# DWM1000_Feather.net
KiCad netlist of a schematic drawn in EAGLE
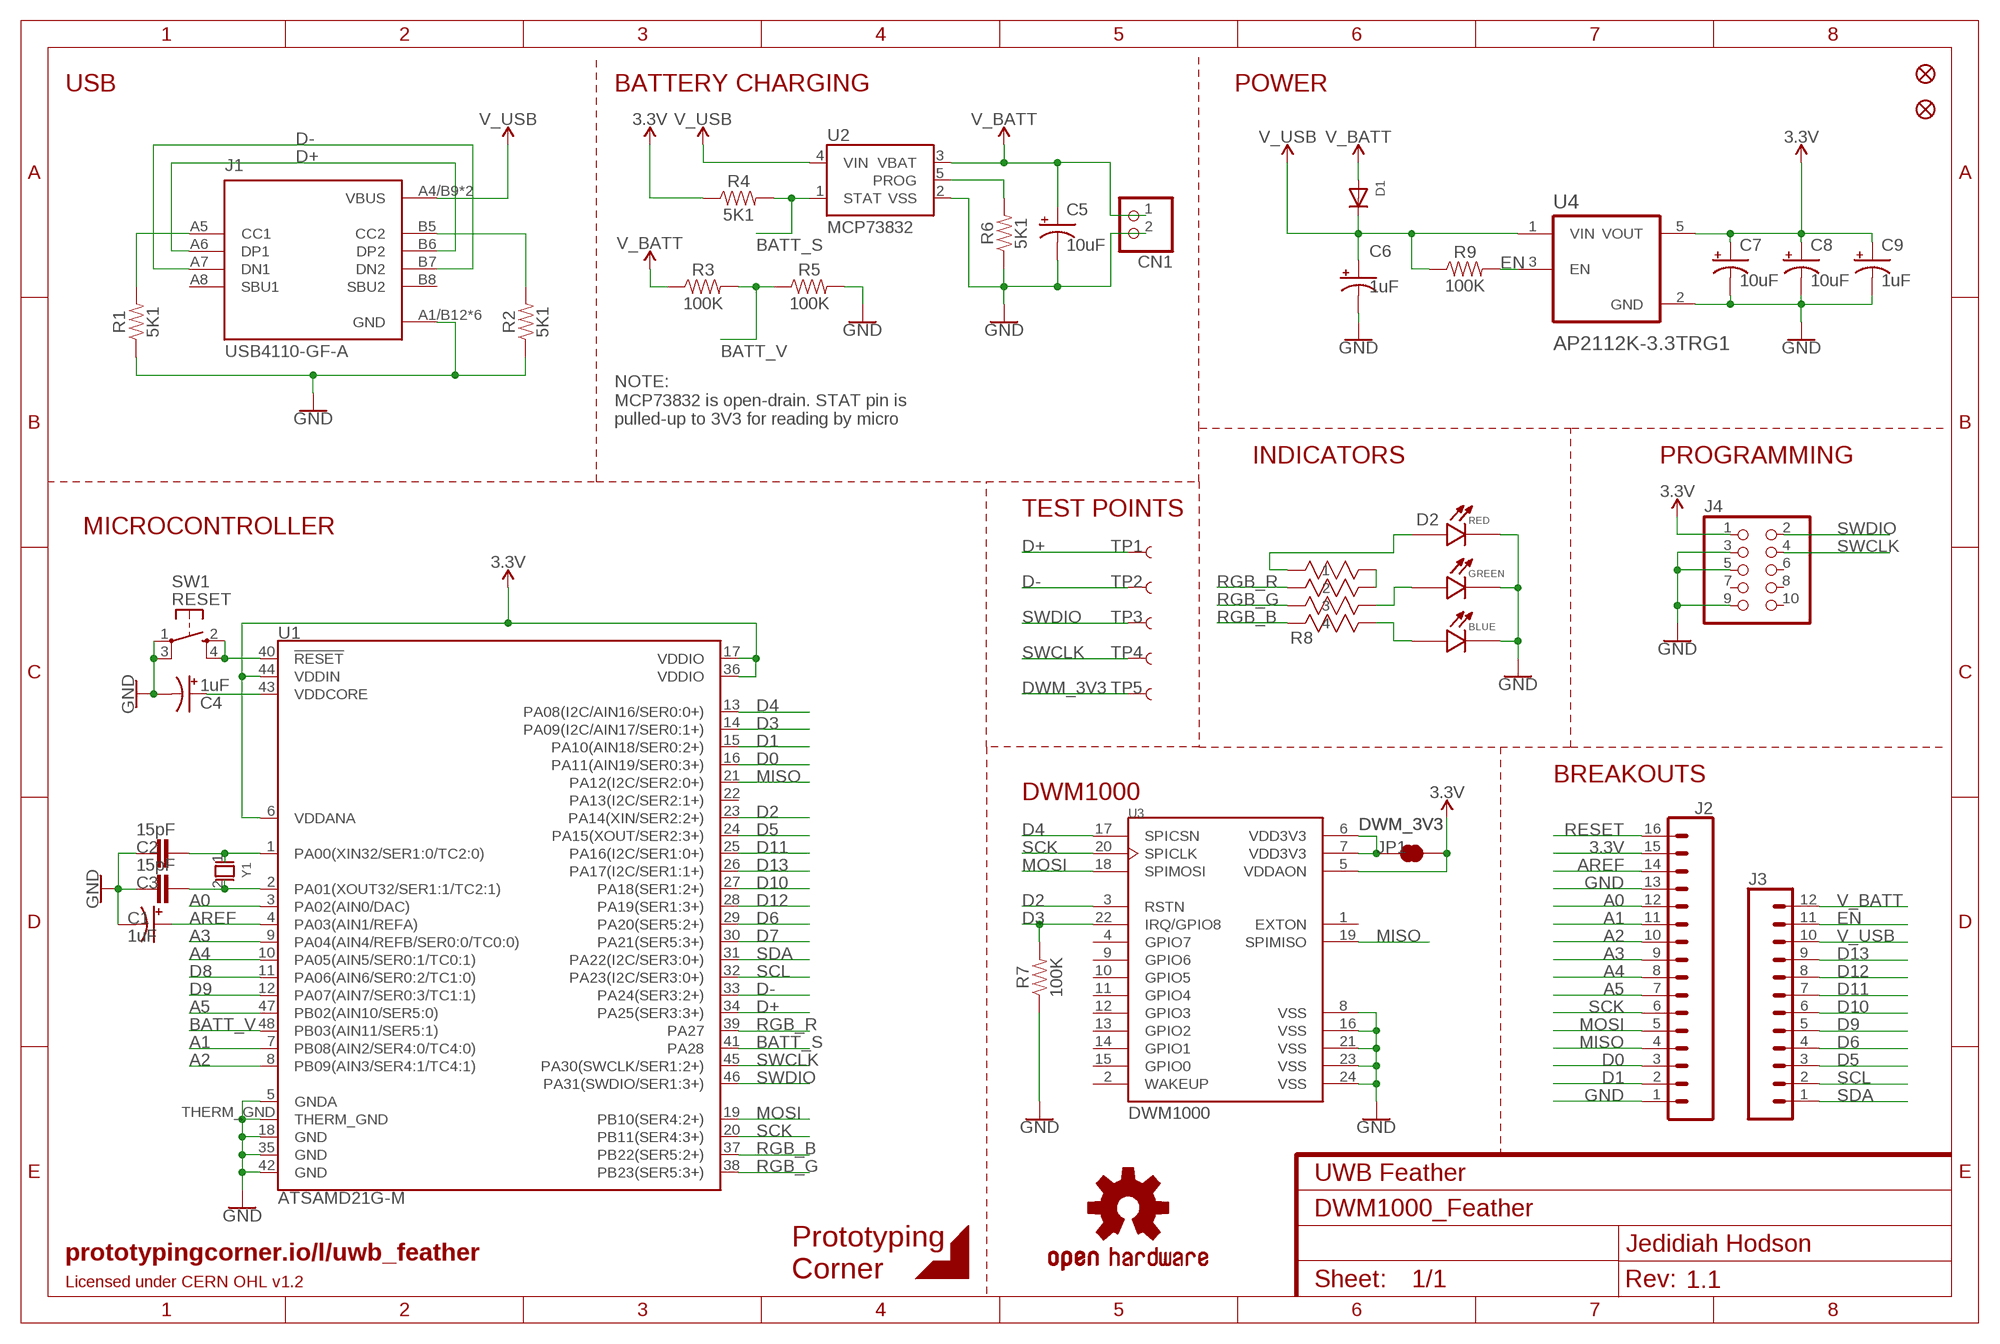
[diagram p0: schematic, sheet 1]

(export (version "E")
  (design (tool "Eeschema 10.0.6"))
  (components
    (comp (ref "C1")
      (value "1uF")
      (footprint "eagle-import:0603-POLAR")
      (libsource (lib "eagle-import") (part "10UF-POLAR-0603-6.3V-20%(TANT)"))
    )
    (comp (ref "C2")
      (value "15pF")
      (footprint "eagle-import:0402")
      (libsource (lib "eagle-import") (part "15PF-0402-50V-5%"))
    )
    (comp (ref "C3")
      (value "15pF")
      (footprint "eagle-import:0402")
      (libsource (lib "eagle-import") (part "15PF-0402-50V-5%"))
    )
    (comp (ref "C4")
      (value "1uF")
      (footprint "eagle-import:0603-POLAR")
      (libsource (lib "eagle-import") (part "10UF-POLAR-0603-6.3V-20%(TANT)"))
    )
    (comp (ref "C5")
      (value "10uF")
      (footprint "eagle-import:0603-POLAR")
      (libsource (lib "eagle-import") (part "10UF-POLAR-0603-6.3V-20%(TANT)"))
    )
    (comp (ref "C6")
      (value "1uF")
      (footprint "eagle-import:0603-POLAR")
      (libsource (lib "eagle-import") (part "10UF-POLAR-0603-6.3V-20%(TANT)"))
    )
    (comp (ref "C7")
      (value "10uF")
      (footprint "eagle-import:0603-POLAR")
      (libsource (lib "eagle-import") (part "10UF-POLAR-0603-6.3V-20%(TANT)"))
    )
    (comp (ref "C8")
      (value "10uF")
      (footprint "eagle-import:0603-POLAR")
      (libsource (lib "eagle-import") (part "10UF-POLAR-0603-6.3V-20%(TANT)"))
    )
    (comp (ref "C9")
      (value "1uF")
      (footprint "eagle-import:0603-POLAR")
      (libsource (lib "eagle-import") (part "10UF-POLAR-0603-6.3V-20%(TANT)"))
    )
    (comp (ref "CN1")
      (value "JST_2PIN-SMT-RA")
      (footprint "eagle-import:JST-PH-2-SMT-RA")
      (libsource (lib "eagle-import") (part "JST_2PIN-SMT-RA"))
    )
    (comp (ref "D1")
      (value "DIODE_SOD-123FL")
      (footprint "eagle-import:SOD-123FL")
      (libsource (lib "eagle-import") (part "DIODE_SOD-123FL"))
    )
    (comp (ref "D2")
      (value "ASMT-YTD7-0AA02")
      (footprint "eagle-import:LED_ASMT-YTD7-0AA02")
      (fields (field (name "MF") "Broadcom Limited"))
      (libsource (lib "eagle-import") (part "ASMT-YTD7-0AA02"))
    )
    (comp (ref "FD1")
      (value "FIDUCIALUFIDUCIAL")
      (footprint "eagle-import:FIDUCIAL-MICRO")
      (libsource (lib "eagle-import") (part "FIDUCIALUFIDUCIAL"))
    )
    (comp (ref "FD2")
      (value "FIDUCIALUFIDUCIAL")
      (footprint "eagle-import:FIDUCIAL-MICRO")
      (libsource (lib "eagle-import") (part "FIDUCIALUFIDUCIAL"))
    )
    (comp (ref "J1")
      (value "USB4110-GF-A")
      (footprint "eagle-import:GCT_USB4110-GF-A")
      (fields (field (name "MF") "GCT"))
      (libsource (lib "eagle-import") (part "USB4110-GF-A"))
    )
    (comp (ref "J2")
      (value "CONN_161X16_NO_SILK")
      (footprint "eagle-import:1X16_NO_SILK")
      (libsource (lib "eagle-import") (part "CONN_161X16_NO_SILK"))
    )
    (comp (ref "J3")
      (value "CONN_12NO_SILK")
      (footprint "eagle-import:1X12_NO_SILK")
      (libsource (lib "eagle-import") (part "CONN_12NO_SILK"))
    )
    (comp (ref "J4")
      (value "20021221-00010C4LF")
      (footprint "eagle-import:20021221-00010C4LF")
      (fields (field (name "DIGI-KEY_PART_NUMBER") "609-3700-1-ND") (field (name "MF") "Amphenol ICC"))
      (libsource (lib "eagle-import") (part "20021221-00010C4LF"))
    )
    (comp (ref "JP1")
      (value "DWM_3V3")
      (footprint "eagle-import:SMT-JUMPER_2_NC_TRACE_SILK")
      (libsource (lib "eagle-import") (part "JUMPER-SMT_2_NC_TRACE_SILK"))
    )
    (comp (ref "LOGO1")
      (value "OSHW-LOGOS")
      (footprint "eagle-import:OSHW-LOGO-S")
      (libsource (lib "eagle-import") (part "OSHW-LOGOS"))
    )
    (comp (ref "R1")
      (value "5K1")
      (footprint "eagle-import:0603")
      (libsource (lib "eagle-import") (part "RESISTOR0603"))
    )
    (comp (ref "R2")
      (value "5K1")
      (footprint "eagle-import:0603")
      (libsource (lib "eagle-import") (part "RESISTOR0603"))
    )
    (comp (ref "R3")
      (value "100K")
      (footprint "eagle-import:0603")
      (libsource (lib "eagle-import") (part "RESISTOR0603"))
    )
    (comp (ref "R4")
      (value "5K1")
      (footprint "eagle-import:0603")
      (libsource (lib "eagle-import") (part "RESISTOR0603"))
    )
    (comp (ref "R5")
      (value "100K")
      (footprint "eagle-import:0603")
      (libsource (lib "eagle-import") (part "RESISTOR0603"))
    )
    (comp (ref "R6")
      (value "5K1")
      (footprint "eagle-import:0603")
      (libsource (lib "eagle-import") (part "RESISTOR0603"))
    )
    (comp (ref "R7")
      (value "100K")
      (footprint "eagle-import:0603")
      (libsource (lib "eagle-import") (part "RESISTOR0603"))
    )
    (comp (ref "R8")
      (value "YC124-JR-07330RL")
      (footprint "eagle-import:YAG_YC124")
      (libsource (lib "eagle-import") (part "YC124-JR-07330RL"))
    )
    (comp (ref "R9")
      (value "100K")
      (footprint "eagle-import:0603")
      (libsource (lib "eagle-import") (part "RESISTOR0603"))
    )
    (comp (ref "SW1")
      (value "SPST_TACT-KMR2")
      (footprint "eagle-import:KMR2")
      (libsource (lib "eagle-import") (part "SPST_TACT-KMR2"))
    )
    (comp (ref "TP1")
      (value "TEST-POINT3")
      (footprint "eagle-import:PAD.03X.03")
      (libsource (lib "eagle-import") (part "TEST-POINT3"))
    )
    (comp (ref "TP2")
      (value "TEST-POINT3")
      (footprint "eagle-import:PAD.03X.03")
      (libsource (lib "eagle-import") (part "TEST-POINT3"))
    )
    (comp (ref "TP3")
      (value "TEST-POINT3")
      (footprint "eagle-import:PAD.03X.03")
      (libsource (lib "eagle-import") (part "TEST-POINT3"))
    )
    (comp (ref "TP4")
      (value "TEST-POINT3")
      (footprint "eagle-import:PAD.03X.03")
      (libsource (lib "eagle-import") (part "TEST-POINT3"))
    )
    (comp (ref "TP5")
      (value "TEST-POINT3")
      (footprint "eagle-import:PAD.03X.03")
      (libsource (lib "eagle-import") (part "TEST-POINT3"))
    )
    (comp (ref "U1")
      (value "ATSAMD21G-M")
      (footprint "eagle-import:QFN-48")
      (libsource (lib "eagle-import") (part "ATSAMD21G-M"))
    )
    (comp (ref "U2")
      (value "MCP73832")
      (footprint "eagle-import:SOT23-5")
      (libsource (lib "eagle-import") (part "MCP73831"))
    )
    (comp (ref "U3")
      (value "DWM1000")
      (footprint "eagle-import:XCVR_DWM1000")
      (fields (field (name "MF") "Decawave Limited"))
      (libsource (lib "eagle-import") (part "DWM1000"))
    )
    (comp (ref "U4")
      (value "AP2112K-3.3TRG1")
      (footprint "eagle-import:SOT95P285X140-5N")
      (fields
        (field (name "DIGI-KEY_PART_NUMBER") "AP2112K-3.3TRG1DICT-ND")
        (field (name "MF") "Diodes Inc.")
      )
      (libsource (lib "eagle-import") (part "AP2112K-3.3TRG1"))
    )
    (comp (ref "Y1")
      (value "FC-135_32.7680KA-A0")
      (footprint "eagle-import:XTAL_FC-135_32.7680KA-A0")
      (fields
        (field (name "DIGI-KEY_PART_NUMBER") "SER4077CT-ND")
        (field (name "MF") "EPSON")
        (field (name "MP") "FC-135 32.7680KA-A0")
      )
      (libsource (lib "eagle-import") (part "FC-135_32.7680KA-A0"))
    )
  )
  (nets
    (net (code "1") (name "/A0") (class "Default")
      (node (ref "J2") (pin "12") (pinfunction "12_12") (pintype "passive"))
      (node (ref "U1") (pin "3") (pinfunction "PA02(AIN0/DAC)_3") (pintype "bidirectional"))
    )
    (net (code "2") (name "/A1") (class "Default")
      (node (ref "J2") (pin "11") (pinfunction "11_11") (pintype "passive"))
      (node (ref "U1") (pin "7") (pinfunction "PB08(AIN2/SER4:0/TC4:0)_7") (pintype "bidirectional"))
    )
    (net (code "3") (name "/A2") (class "Default")
      (node (ref "J2") (pin "10") (pinfunction "10_10") (pintype "passive"))
      (node (ref "U1") (pin "8") (pinfunction "PB09(AIN3/SER4:1/TC4:1)_8") (pintype "bidirectional"))
    )
    (net (code "4") (name "/A3") (class "Default")
      (node (ref "J2") (pin "9") (pinfunction "9_9") (pintype "passive"))
      (node (ref "U1") (pin "9") (pinfunction "PA04(AIN4/REFB/SER0:0/TC0:0)_9") (pintype "bidirectional"))
    )
    (net (code "5") (name "/A4") (class "Default")
      (node (ref "J2") (pin "8") (pinfunction "8_8") (pintype "passive"))
      (node (ref "U1") (pin "10") (pinfunction "PA05(AIN5/SER0:1/TC0:1)_10") (pintype "bidirectional"))
    )
    (net (code "6") (name "/A5") (class "Default")
      (node (ref "J2") (pin "7") (pinfunction "7_7") (pintype "passive"))
      (node (ref "U1") (pin "47") (pinfunction "PB02(AIN10/SER5:0)_47") (pintype "bidirectional"))
    )
    (net (code "7") (name "/AREF") (class "Default")
      (node (ref "C1") (pin "+") (pinfunction "1_+") (pintype "passive"))
      (node (ref "J2") (pin "14") (pinfunction "14_14") (pintype "passive"))
      (node (ref "U1") (pin "4") (pinfunction "PA03(AIN1/REFA)_4") (pintype "bidirectional"))
    )
    (net (code "8") (name "/BATT_S") (class "Default")
      (node (ref "R4") (pin "2") (pinfunction "2_2") (pintype "passive"))
      (node (ref "U1") (pin "41") (pinfunction "PA28_41") (pintype "bidirectional"))
      (node (ref "U2") (pin "1") (pinfunction "STAT_1") (pintype "output"))
    )
    (net (code "9") (name "/BATT_V") (class "Default")
      (node (ref "R3") (pin "2") (pinfunction "2_2") (pintype "passive"))
      (node (ref "R5") (pin "1") (pinfunction "1_1") (pintype "passive"))
      (node (ref "U1") (pin "48") (pinfunction "PB03(AIN11/SER5:1)_48") (pintype "bidirectional"))
    )
    (net (code "10") (name "/D+") (class "Default")
      (node (ref "J1") (pin "A6") (pinfunction "DP1_A6") (pintype "bidirectional"))
      (node (ref "J1") (pin "B6") (pinfunction "DP2_B6") (pintype "bidirectional"))
      (node (ref "TP1") (pin "P$1") (pinfunction "1_P$1") (pintype "bidirectional"))
      (node (ref "U1") (pin "34") (pinfunction "PA25(SER3:3+)_34") (pintype "bidirectional"))
    )
    (net (code "11") (name "/D-") (class "Default")
      (node (ref "J1") (pin "A7") (pinfunction "DN1_A7") (pintype "bidirectional"))
      (node (ref "J1") (pin "B7") (pinfunction "DN2_B7") (pintype "bidirectional"))
      (node (ref "TP2") (pin "P$1") (pinfunction "1_P$1") (pintype "bidirectional"))
      (node (ref "U1") (pin "33") (pinfunction "PA24(SER3:2+)_33") (pintype "bidirectional"))
    )
    (net (code "12") (name "/D0") (class "Default")
      (node (ref "J2") (pin "3") (pinfunction "3_3") (pintype "passive"))
      (node (ref "U1") (pin "16") (pinfunction "PA11(AIN19/SER0:3+)_16") (pintype "bidirectional"))
    )
    (net (code "13") (name "/D1") (class "Default")
      (node (ref "J2") (pin "2") (pinfunction "2_2") (pintype "passive"))
      (node (ref "U1") (pin "15") (pinfunction "PA10(AIN18/SER0:2+)_15") (pintype "bidirectional"))
    )
    (net (code "14") (name "/D2") (class "Default")
      (node (ref "U1") (pin "23") (pinfunction "PA14(XIN/SER2:2+)_23") (pintype "bidirectional"))
      (node (ref "U3") (pin "3") (pinfunction "RSTN_3") (pintype "bidirectional"))
    )
    (net (code "15") (name "/D3") (class "Default")
      (node (ref "R7") (pin "2") (pinfunction "2_2") (pintype "passive"))
      (node (ref "U1") (pin "14") (pinfunction "PA09(I2C/AIN17/SER0:1+)_14") (pintype "bidirectional"))
      (node (ref "U3") (pin "22") (pinfunction "IRQ/GPIO8_22") (pintype "bidirectional"))
    )
    (net (code "16") (name "/D4") (class "Default")
      (node (ref "U1") (pin "13") (pinfunction "PA08(I2C/AIN16/SER0:0+)_13") (pintype "bidirectional"))
      (node (ref "U3") (pin "17") (pinfunction "SPICSN_17") (pintype "input"))
    )
    (net (code "17") (name "/D5") (class "Default")
      (node (ref "J3") (pin "3") (pinfunction "3_3") (pintype "passive"))
      (node (ref "U1") (pin "24") (pinfunction "PA15(XOUT/SER2:3+)_24") (pintype "bidirectional"))
    )
    (net (code "18") (name "/D6") (class "Default")
      (node (ref "J3") (pin "4") (pinfunction "4_4") (pintype "passive"))
      (node (ref "U1") (pin "29") (pinfunction "PA20(SER5:2+)_29") (pintype "bidirectional"))
    )
    (net (code "19") (name "/D7") (class "Default")
      (node (ref "U1") (pin "30") (pinfunction "PA21(SER5:3+)_30") (pintype "bidirectional"))
    )
    (net (code "20") (name "/D8") (class "Default")
      (node (ref "U1") (pin "11") (pinfunction "PA06(AIN6/SER0:2/TC1:0)_11") (pintype "bidirectional"))
    )
    (net (code "21") (name "/D9") (class "Default")
      (node (ref "J3") (pin "5") (pinfunction "5_5") (pintype "passive"))
      (node (ref "U1") (pin "12") (pinfunction "PA07(AIN7/SER0:3/TC1:1)_12") (pintype "bidirectional"))
    )
    (net (code "22") (name "/D10") (class "Default")
      (node (ref "J3") (pin "6") (pinfunction "6_6") (pintype "passive"))
      (node (ref "U1") (pin "27") (pinfunction "PA18(SER1:2+)_27") (pintype "bidirectional"))
    )
    (net (code "23") (name "/D11") (class "Default")
      (node (ref "J3") (pin "7") (pinfunction "7_7") (pintype "passive"))
      (node (ref "U1") (pin "25") (pinfunction "PA16(I2C/SER1:0+)_25") (pintype "bidirectional"))
    )
    (net (code "24") (name "/D12") (class "Default")
      (node (ref "J3") (pin "8") (pinfunction "8_8") (pintype "passive"))
      (node (ref "U1") (pin "28") (pinfunction "PA19(SER1:3+)_28") (pintype "bidirectional"))
    )
    (net (code "25") (name "/D13") (class "Default")
      (node (ref "J3") (pin "9") (pinfunction "9_9") (pintype "passive"))
      (node (ref "U1") (pin "26") (pinfunction "PA17(I2C/SER1:1+)_26") (pintype "bidirectional"))
    )
    (net (code "26") (name "/DWM_3V3") (class "Default")
      (node (ref "JP1") (pin "1") (pinfunction "1_1") (pintype "passive"))
      (node (ref "TP5") (pin "P$1") (pinfunction "1_P$1") (pintype "bidirectional"))
      (node (ref "U3") (pin "6") (pinfunction "VDD3V3_6") (pintype "power_in"))
      (node (ref "U3") (pin "7") (pinfunction "VDD3V3_7") (pintype "power_in"))
    )
    (net (code "27") (name "/EN") (class "Default")
      (node (ref "J3") (pin "11") (pinfunction "11_11") (pintype "passive"))
      (node (ref "R9") (pin "2") (pinfunction "2_2") (pintype "passive"))
      (node (ref "U4") (pin "3") (pinfunction "EN_3") (pintype "input"))
    )
    (net (code "28") (name "/MISO") (class "Default")
      (node (ref "J2") (pin "4") (pinfunction "4_4") (pintype "passive"))
      (node (ref "U1") (pin "21") (pinfunction "PA12(I2C/SER2:0+)_21") (pintype "bidirectional"))
      (node (ref "U3") (pin "19") (pinfunction "SPIMISO_19") (pintype "output"))
    )
    (net (code "29") (name "/MOSI") (class "Default")
      (node (ref "J2") (pin "5") (pinfunction "5_5") (pintype "passive"))
      (node (ref "U1") (pin "19") (pinfunction "PB10(SER4:2+)_19") (pintype "bidirectional"))
      (node (ref "U3") (pin "18") (pinfunction "SPIMOSI_18") (pintype "input"))
    )
    (net (code "30") (name "/RESET") (class "Default")
      (node (ref "J2") (pin "16") (pinfunction "16_16") (pintype "passive"))
      (node (ref "SW1") (pin "2") (pinfunction "S_2") (pintype "passive"))
      (node (ref "SW1") (pin "4") (pinfunction "S1_4") (pintype "passive"))
      (node (ref "U1") (pin "40") (pinfunction "~{RESET}_40") (pintype "bidirectional"))
    )
    (net (code "31") (name "/RGB_B") (class "Default")
      (node (ref "R8") (pin "4") (pinfunction "4_4") (pintype "passive"))
      (node (ref "U1") (pin "37") (pinfunction "PB22(SER5:2+)_37") (pintype "bidirectional"))
    )
    (net (code "32") (name "/RGB_G") (class "Default")
      (node (ref "R8") (pin "3") (pinfunction "3_3") (pintype "passive"))
      (node (ref "U1") (pin "38") (pinfunction "PB23(SER5:3+)_38") (pintype "bidirectional"))
    )
    (net (code "33") (name "/RGB_R") (class "Default")
      (node (ref "R8") (pin "2") (pinfunction "2_2") (pintype "passive"))
      (node (ref "U1") (pin "39") (pinfunction "PA27_39") (pintype "bidirectional"))
    )
    (net (code "34") (name "/SCK") (class "Default")
      (node (ref "J2") (pin "6") (pinfunction "6_6") (pintype "passive"))
      (node (ref "U1") (pin "20") (pinfunction "PB11(SER4:3+)_20") (pintype "bidirectional"))
      (node (ref "U3") (pin "20") (pinfunction "SPICLK_20") (pintype "input"))
    )
    (net (code "35") (name "/SCL") (class "Default")
      (node (ref "J3") (pin "2") (pinfunction "2_2") (pintype "passive"))
      (node (ref "U1") (pin "32") (pinfunction "PA23(I2C/SER3:0+)_32") (pintype "bidirectional"))
    )
    (net (code "36") (name "/SDA") (class "Default")
      (node (ref "J3") (pin "1") (pinfunction "1_1") (pintype "passive"))
      (node (ref "U1") (pin "31") (pinfunction "PA22(I2C/SER3:0+)_31") (pintype "bidirectional"))
    )
    (net (code "37") (name "/SWCLK") (class "Default")
      (node (ref "J4") (pin "4") (pinfunction "4_4") (pintype "passive"))
      (node (ref "TP4") (pin "P$1") (pinfunction "1_P$1") (pintype "bidirectional"))
      (node (ref "U1") (pin "45") (pinfunction "PA30(SWCLK/SER1:2+)_45") (pintype "bidirectional"))
    )
    (net (code "38") (name "/SWDIO") (class "Default")
      (node (ref "J4") (pin "2") (pinfunction "2_2") (pintype "passive"))
      (node (ref "TP3") (pin "P$1") (pinfunction "1_P$1") (pintype "bidirectional"))
      (node (ref "U1") (pin "46") (pinfunction "PA31(SWDIO/SER1:3+)_46") (pintype "bidirectional"))
    )
    (net (code "39") (name "3.3V") (class "Default")
      (node (ref "C7") (pin "+") (pinfunction "1_+") (pintype "passive"))
      (node (ref "C8") (pin "+") (pinfunction "1_+") (pintype "passive"))
      (node (ref "C9") (pin "+") (pinfunction "1_+") (pintype "passive"))
      (node (ref "J2") (pin "15") (pinfunction "15_15") (pintype "passive"))
      (node (ref "J4") (pin "1") (pinfunction "1_1") (pintype "passive"))
      (node (ref "JP1") (pin "2") (pinfunction "2_2") (pintype "passive"))
      (node (ref "R4") (pin "1") (pinfunction "1_1") (pintype "passive"))
      (node (ref "U1") (pin "17") (pinfunction "VDDIO_17") (pintype "bidirectional"))
      (node (ref "U1") (pin "36") (pinfunction "VDDIO_36") (pintype "bidirectional"))
      (node (ref "U1") (pin "44") (pinfunction "VDDIN_44") (pintype "bidirectional"))
      (node (ref "U1") (pin "6") (pinfunction "VDDANA_6") (pintype "bidirectional"))
      (node (ref "U3") (pin "5") (pinfunction "VDDAON_5") (pintype "power_in"))
      (node (ref "U4") (pin "5") (pinfunction "VOUT_5") (pintype "power_in"))
    )
    (net (code "40") (name "GND") (class "Default")
      (node (ref "C1") (pin "-") (pinfunction "2_-") (pintype "passive"))
      (node (ref "C2") (pin "1") (pinfunction "1_1") (pintype "passive"))
      (node (ref "C3") (pin "1") (pinfunction "1_1") (pintype "passive"))
      (node (ref "C4") (pin "-") (pinfunction "2_-") (pintype "passive"))
      (node (ref "C5") (pin "-") (pinfunction "2_-") (pintype "passive"))
      (node (ref "C6") (pin "-") (pinfunction "2_-") (pintype "passive"))
      (node (ref "C7") (pin "-") (pinfunction "2_-") (pintype "passive"))
      (node (ref "C8") (pin "-") (pinfunction "2_-") (pintype "passive"))
      (node (ref "C9") (pin "-") (pinfunction "2_-") (pintype "passive"))
      (node (ref "CN1") (pin "2") (pinfunction "1_2") (pintype "passive"))
      (node (ref "D2") (pin "1") (pinfunction "B_C_1") (pintype "passive"))
      (node (ref "D2") (pin "2") (pinfunction "G_C_2") (pintype "passive"))
      (node (ref "D2") (pin "3") (pinfunction "R_C_3") (pintype "passive"))
      (node (ref "J1") (pin "A1/B12") (pinfunction "GND_A1/B12") (pintype "power_in"))
      (node (ref "J1") (pin "B1/A12") (pinfunction "GND_B1/A12") (pintype "power_in"))
      (node (ref "J1") (pin "S1") (pinfunction "GND_S1") (pintype "power_in"))
      (node (ref "J1") (pin "S2") (pinfunction "GND_S2") (pintype "power_in"))
      (node (ref "J1") (pin "S3") (pinfunction "GND_S3") (pintype "power_in"))
      (node (ref "J1") (pin "S4") (pinfunction "GND_S4") (pintype "power_in"))
      (node (ref "J2") (pin "1") (pinfunction "1_1") (pintype "passive"))
      (node (ref "J2") (pin "13") (pinfunction "13_13") (pintype "passive"))
      (node (ref "J4") (pin "3") (pinfunction "3_3") (pintype "passive"))
      (node (ref "J4") (pin "5") (pinfunction "5_5") (pintype "passive"))
      (node (ref "J4") (pin "9") (pinfunction "9_9") (pintype "passive"))
      (node (ref "R1") (pin "1") (pinfunction "1_1") (pintype "passive"))
      (node (ref "R2") (pin "1") (pinfunction "1_1") (pintype "passive"))
      (node (ref "R5") (pin "2") (pinfunction "2_2") (pintype "passive"))
      (node (ref "R6") (pin "1") (pinfunction "1_1") (pintype "passive"))
      (node (ref "R7") (pin "1") (pinfunction "1_1") (pintype "passive"))
      (node (ref "SW1") (pin "1") (pinfunction "P_1") (pintype "passive"))
      (node (ref "SW1") (pin "3") (pinfunction "P1_3") (pintype "passive"))
      (node (ref "U1") (pin "18") (pinfunction "GND_18") (pintype "bidirectional"))
      (node (ref "U1") (pin "35") (pinfunction "GND_35") (pintype "bidirectional"))
      (node (ref "U1") (pin "42") (pinfunction "GND_42") (pintype "bidirectional"))
      (node (ref "U1") (pin "5") (pinfunction "GNDA_5") (pintype "bidirectional"))
      (node (ref "U1") (pin "THERM_GND") (pinfunction "THERM_GND_THERM_GND") (pintype "bidirectional"))
      (node (ref "U2") (pin "2") (pinfunction "VSS_2") (pintype "power_in"))
      (node (ref "U3") (pin "16") (pinfunction "VSS_16") (pintype "power_in"))
      (node (ref "U3") (pin "21") (pinfunction "VSS_21") (pintype "power_in"))
      (node (ref "U3") (pin "23") (pinfunction "VSS_23") (pintype "power_in"))
      (node (ref "U3") (pin "24") (pinfunction "VSS_24") (pintype "power_in"))
      (node (ref "U3") (pin "8") (pinfunction "VSS_8") (pintype "power_in"))
      (node (ref "U4") (pin "2") (pinfunction "GND_2") (pintype "power_in"))
    )
    (net (code "41") (name "Net-(C4-1)") (class "Default")
      (node (ref "C4") (pin "+") (pinfunction "1_+") (pintype "passive"))
      (node (ref "U1") (pin "43") (pinfunction "VDDCORE_43") (pintype "bidirectional"))
    )
    (net (code "42") (name "Net-(D2-B_A)") (class "Default")
      (node (ref "D2") (pin "6") (pinfunction "B_A_6") (pintype "passive"))
      (node (ref "R8") (pin "5") (pinfunction "5_5") (pintype "passive"))
    )
    (net (code "43") (name "Net-(D2-G_A)") (class "Default")
      (node (ref "D2") (pin "5") (pinfunction "G_A_5") (pintype "passive"))
      (node (ref "R8") (pin "6") (pinfunction "6_6") (pintype "passive"))
    )
    (net (code "44") (name "Net-(D2-R_A)") (class "Default")
      (node (ref "D2") (pin "4") (pinfunction "R_A_4") (pintype "passive"))
      (node (ref "R8") (pin "1") (pinfunction "1_1") (pintype "passive"))
    )
    (net (code "45") (name "Net-(J1-CC1)") (class "Default")
      (node (ref "J1") (pin "A5") (pinfunction "CC1_A5") (pintype "bidirectional"))
      (node (ref "R1") (pin "2") (pinfunction "2_2") (pintype "passive"))
    )
    (net (code "46") (name "Net-(J1-CC2)") (class "Default")
      (node (ref "J1") (pin "B5") (pinfunction "CC2_B5") (pintype "bidirectional"))
      (node (ref "R2") (pin "2") (pinfunction "2_2") (pintype "passive"))
    )
    (net (code "47") (name "Net-(R8-Pad7)") (class "Default")
      (node (ref "R8") (pin "7") (pinfunction "7_7") (pintype "passive"))
      (node (ref "R8") (pin "8") (pinfunction "8_8") (pintype "passive"))
    )
    (net (code "48") (name "Net-(U1-PA00(XIN32{slash}SER1:0{slash}TC2:0))") (class "Default")
      (node (ref "C2") (pin "2") (pinfunction "2_2") (pintype "passive"))
      (node (ref "U1") (pin "1") (pinfunction "PA00(XIN32/SER1:0/TC2:0)_1") (pintype "bidirectional"))
      (node (ref "Y1") (pin "1") (pinfunction "1_1") (pintype "passive"))
    )
    (net (code "49") (name "Net-(U1-PA01(XOUT32{slash}SER1:1{slash}TC2:1))") (class "Default")
      (node (ref "C3") (pin "2") (pinfunction "2_2") (pintype "passive"))
      (node (ref "U1") (pin "2") (pinfunction "PA01(XOUT32/SER1:1/TC2:1)_2") (pintype "bidirectional"))
      (node (ref "Y1") (pin "2") (pinfunction "2_2") (pintype "passive"))
    )
    (net (code "50") (name "Net-(U2-PROG)") (class "Default")
      (node (ref "R6") (pin "2") (pinfunction "2_2") (pintype "passive"))
      (node (ref "U2") (pin "5") (pinfunction "PROG_5") (pintype "input"))
    )
    (net (code "51") (name "V_BATT") (class "Default")
      (node (ref "C5") (pin "+") (pinfunction "1_+") (pintype "passive"))
      (node (ref "CN1") (pin "1") (pinfunction "2_1") (pintype "passive"))
      (node (ref "D1") (pin "A") (pinfunction "A_A") (pintype "passive"))
      (node (ref "J3") (pin "12") (pinfunction "12_12") (pintype "passive"))
      (node (ref "R3") (pin "1") (pinfunction "1_1") (pintype "passive"))
      (node (ref "U2") (pin "3") (pinfunction "VBAT_3") (pintype "power_in"))
    )
    (net (code "52") (name "V_USB") (class "Default")
      (node (ref "C6") (pin "+") (pinfunction "1_+") (pintype "passive"))
      (node (ref "D1") (pin "C") (pinfunction "C_C") (pintype "passive"))
      (node (ref "J1") (pin "A4/B9") (pinfunction "VBUS_A4/B9") (pintype "power_in"))
      (node (ref "J1") (pin "B4/A9") (pinfunction "VBUS_B4/A9") (pintype "power_in"))
      (node (ref "J3") (pin "10") (pinfunction "10_10") (pintype "passive"))
      (node (ref "R9") (pin "1") (pinfunction "1_1") (pintype "passive"))
      (node (ref "U2") (pin "4") (pinfunction "VIN_4") (pintype "power_in"))
      (node (ref "U4") (pin "1") (pinfunction "VIN_1") (pintype "power_in"))
    )
    (net (code "53") (name "unconnected-(J1-SBU1-PadA8)") (class "Default")
      (node (ref "J1") (pin "A8") (pinfunction "SBU1_A8") (pintype "bidirectional"))
    )
    (net (code "54") (name "unconnected-(J1-SBU2-PadB8)") (class "Default")
      (node (ref "J1") (pin "B8") (pinfunction "SBU2_B8") (pintype "bidirectional"))
    )
    (net (code "55") (name "unconnected-(J4-Pad6)") (class "Default")
      (node (ref "J4") (pin "6") (pinfunction "6_6") (pintype "passive"))
    )
    (net (code "56") (name "unconnected-(J4-Pad7)") (class "Default")
      (node (ref "J4") (pin "7") (pinfunction "7_7") (pintype "passive"))
    )
    (net (code "57") (name "unconnected-(J4-Pad8)") (class "Default")
      (node (ref "J4") (pin "8") (pinfunction "8_8") (pintype "passive"))
    )
    (net (code "58") (name "unconnected-(J4-Pad10)") (class "Default")
      (node (ref "J4") (pin "10") (pinfunction "10_10") (pintype "passive"))
    )
    (net (code "59") (name "unconnected-(U1-PA13(I2C{slash}SER2:1+)-Pad22)") (class "Default")
      (node (ref "U1") (pin "22") (pinfunction "PA13(I2C/SER2:1+)_22") (pintype "bidirectional"))
    )
    (net (code "60") (name "unconnected-(U3-EXTON-Pad1)") (class "Default")
      (node (ref "U3") (pin "1") (pinfunction "EXTON_1") (pintype "output"))
    )
    (net (code "61") (name "unconnected-(U3-GPIO0-Pad15)") (class "Default")
      (node (ref "U3") (pin "15") (pinfunction "GPIO0_15") (pintype "bidirectional"))
    )
    (net (code "62") (name "unconnected-(U3-GPIO1-Pad14)") (class "Default")
      (node (ref "U3") (pin "14") (pinfunction "GPIO1_14") (pintype "bidirectional"))
    )
    (net (code "63") (name "unconnected-(U3-GPIO2-Pad13)") (class "Default")
      (node (ref "U3") (pin "13") (pinfunction "GPIO2_13") (pintype "bidirectional"))
    )
    (net (code "64") (name "unconnected-(U3-GPIO3-Pad12)") (class "Default")
      (node (ref "U3") (pin "12") (pinfunction "GPIO3_12") (pintype "bidirectional"))
    )
    (net (code "65") (name "unconnected-(U3-GPIO4-Pad11)") (class "Default")
      (node (ref "U3") (pin "11") (pinfunction "GPIO4_11") (pintype "bidirectional"))
    )
    (net (code "66") (name "unconnected-(U3-GPIO5-Pad10)") (class "Default")
      (node (ref "U3") (pin "10") (pinfunction "GPIO5_10") (pintype "bidirectional"))
    )
    (net (code "67") (name "unconnected-(U3-GPIO6-Pad9)") (class "Default")
      (node (ref "U3") (pin "9") (pinfunction "GPIO6_9") (pintype "bidirectional"))
    )
    (net (code "68") (name "unconnected-(U3-GPIO7-Pad4)") (class "Default")
      (node (ref "U3") (pin "4") (pinfunction "GPIO7_4") (pintype "bidirectional"))
    )
    (net (code "69") (name "unconnected-(U3-WAKEUP-Pad2)") (class "Default")
      (node (ref "U3") (pin "2") (pinfunction "WAKEUP_2") (pintype "bidirectional"))
    )
  )
)
